# MASTER.net
KiCad netlist of a schematic drawn in Altium Designer
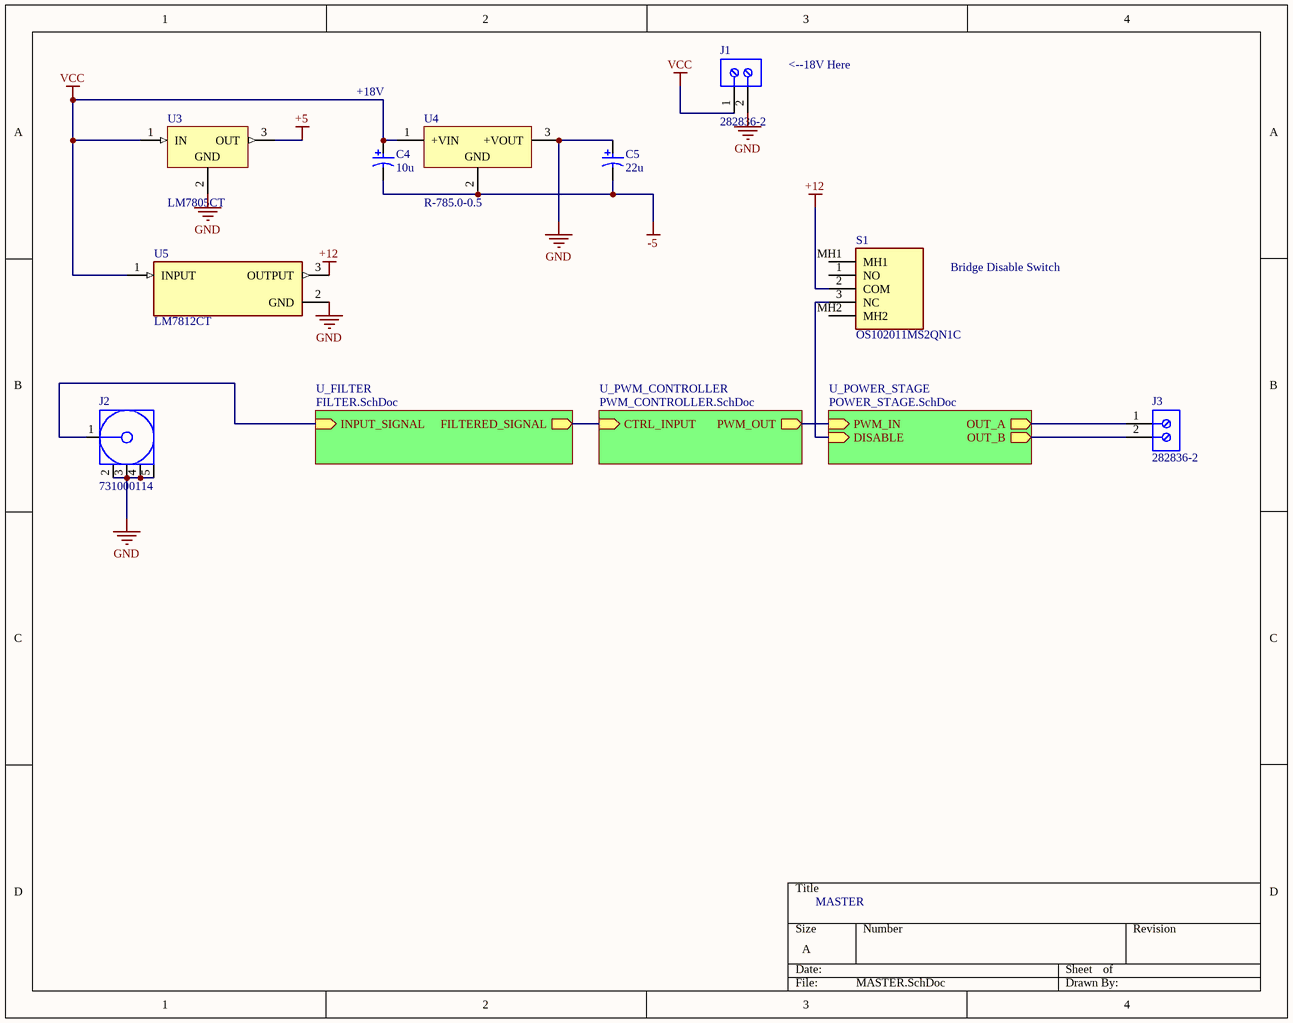
[diagram p0: MASTER.SchDoc]

(export (version "E")
  (design (tool "Eeschema 10.0.6"))
  (components
    (comp (ref "C4")
      (value "10u")
      (footprint "PNSC-ECA-1VM221-2")
      (description "Aluminum Electrolytic Capacitor, 220 uF, +/- 20%, 35 V, -40 to 85 degC, 2-Pin THD, RoHS, Bulk")
      (fields (field (name "MANUFACTURER") "Panasonic"))
      (libsource (lib "Altium Content Vault") (part "CAP-P-2"))
    )
    (comp (ref "C5")
      (value "22u")
      (footprint "PNSC-ECA-1VM221-2")
      (description "Aluminum Electrolytic Capacitor, 220 uF, +/- 20%, 35 V, -40 to 85 degC, 2-Pin THD, RoHS, Bulk")
      (fields (field (name "MANUFACTURER") "Panasonic"))
      (libsource (lib "Altium Content Vault") (part "CAP-P-2"))
    )
    (comp (ref "J1")
      (value "282836-2")
      (footprint "TECO-282836-2_V")
      (description "Female Header, Pitch 5 mm, 1 x 2 Position, Height 10 mm, Tail Length 3.5 mm, Rohs, Bulk")
      (fields (field (name "VOLTAGE") "300V") (field (name "MANUFACTURER") "TE Connectivity"))
      (libsource (lib "Altium Content Vault") (part "CN-1P-F-TB2"))
    )
    (comp (ref "J2")
      (value "731000114")
      (footprint "MOLX-731000114_V")
      (description "SMA Right-Angle PCB Jack Receptacle, Brass Body, Gold Plated, 50 Ohm, 5-Pin THD, RoHS, Tray")
      (fields (field (name "MANUFACTURER") "Molex"))
      (libsource (lib "Altium Content Vault") (part "CN-S-4F-RF5"))
    )
    (comp (ref "J3")
      (value "282836-2")
      (footprint "TECO-282836-2_V")
      (description "Female Header, Pitch 5 mm, 1 x 2 Position, Height 10 mm, Tail Length 3.5 mm, Rohs, Bulk")
      (fields (field (name "VOLTAGE") "300V") (field (name "MANUFACTURER") "TE Connectivity"))
      (libsource (lib "Altium Content Vault") (part "CN-1P-F-TB2"))
    )
    (comp (ref "S1")
      (value "OS102011MS2QN1C")
      (footprint "SamacSys:OS102011MS2QN1C")
      (description "Switch")
      (fields (field (name "MOUSER PART NUMBER") "611-OS102011MS2QN1C"))
      (libsource (lib "*") (part "OS102011MS2QN1C"))
    )
    (comp (ref "U3")
      (value "LM7805CT")
      (footprint "FAIR-TO-220-3")
      (description "Positive Voltage Regulator, 5 V, 1 A, -40 to 125 degC, 3-Pin TO-220, RoHS, Tube")
      (fields (field (name "MANUFACTURER") "FairchildSemiconductor"))
      (libsource (lib "Altium Content Vault") (part "FAIR-LM7805CT-TO220-3"))
    )
    (comp (ref "U4")
      (value "R-785.0-0.5")
      (footprint "REPO-R-78XX-3_V")
      (description "DC/DC-Converter, 5 V Single Output, 500 mA, -40 to 85 degC, 3-Pin THD, RoHS, Tube")
      (fields (field (name "MANUFACTURER") "Recom Power"))
      (libsource (lib "Altium Content Vault") (part "REPO-R-78XX-3"))
    )
    (comp (ref "U5")
      (value "LM7812CT")
      (footprint "FP-TO220B03-MFG")
      (description "IC REG LINEAR 12V 1A TO220-3")
      (fields
        (field (name "OCTOPART") "https://octopart.com/lm7812ct-on+semiconductor-14383031")
        (field (name "OBSOLETE PART") "true")
      )
      (libsource (lib "Altium Content Vault") (part "6207a8f1a6b4db326a9e0a8a99b4969"))
    )
  )
  (nets
    (net (code "1") (name "+5") (class "Default")
      (node (ref "U3") (pin "3") (pinfunction "OUT_3") (pintype "output"))
    )
    (net (code "2") (name "+12") (class "Default")
      (node (ref "S1") (pin "2") (pinfunction "COM_2") (pintype "passive"))
      (node (ref "U5") (pin "3") (pinfunction "OUTPUT_3") (pintype "output"))
    )
    (net (code "3") (name "-5") (class "Default")
      (node (ref "C4") (pin "2") (pinfunction "2_2") (pintype "passive"))
      (node (ref "C5") (pin "2") (pinfunction "2_2") (pintype "passive"))
      (node (ref "U4") (pin "2") (pinfunction "GND_2") (pintype "power_in"))
    )
    (net (code "4") (name "/DISABLE") (class "Default")
      (node (ref "S1") (pin "3") (pinfunction "NC_3") (pintype "passive"))
    )
    (net (code "6") (name "/INPUT_SIGNAL") (class "Default")
      (node (ref "J2") (pin "1") (pinfunction "1_1") (pintype "passive"))
    )
    (net (code "7") (name "/OUT_A") (class "Default")
      (node (ref "J3") (pin "1") (pinfunction "1_1") (pintype "passive"))
    )
    (net (code "8") (name "/OUT_B") (class "Default")
      (node (ref "J3") (pin "2") (pinfunction "2_2") (pintype "passive"))
    )
    (net (code "10") (name "GND") (class "Default")
      (node (ref "C5") (pin "1") (pinfunction "1_1") (pintype "passive"))
      (node (ref "J1") (pin "2") (pinfunction "2_2") (pintype "passive"))
      (node (ref "J2") (pin "2") (pinfunction "2_2") (pintype "passive"))
      (node (ref "J2") (pin "3") (pinfunction "3_3") (pintype "passive"))
      (node (ref "J2") (pin "4") (pinfunction "4_4") (pintype "passive"))
      (node (ref "J2") (pin "5") (pinfunction "5_5") (pintype "passive"))
      (node (ref "U3") (pin "2") (pinfunction "GND_2") (pintype "power_in"))
      (node (ref "U4") (pin "3") (pinfunction "+VOUT_3") (pintype "power_in"))
      (node (ref "U5") (pin "2") (pinfunction "GND_2") (pintype "power_in"))
    )
    (net (code "11") (name "VCC") (class "Default")
      (node (ref "C4") (pin "1") (pinfunction "1_1") (pintype "passive"))
      (node (ref "J1") (pin "1") (pinfunction "1_1") (pintype "passive"))
      (node (ref "U3") (pin "1") (pinfunction "IN_1") (pintype "input"))
      (node (ref "U4") (pin "1") (pinfunction "+VIN_1") (pintype "power_in"))
      (node (ref "U5") (pin "1") (pinfunction "INPUT_1") (pintype "input"))
    )
    (net (code "12") (name "unconnected-(S1-NO-Pad1)") (class "Default")
      (node (ref "S1") (pin "1") (pinfunction "NO_1") (pintype "passive"))
    )
    (net (code "13") (name "unconnected-(S1-PadMH1)") (class "Default")
      (node (ref "S1") (pin "MH1") (pinfunction "MH1_MH1") (pintype "passive"))
    )
    (net (code "14") (name "unconnected-(S1-PadMH2)") (class "Default")
      (node (ref "S1") (pin "MH2") (pinfunction "MH2_MH2") (pintype "passive"))
    )
  )
)
